# distribution.net
KiCad netlist of a schematic drawn in EAGLE
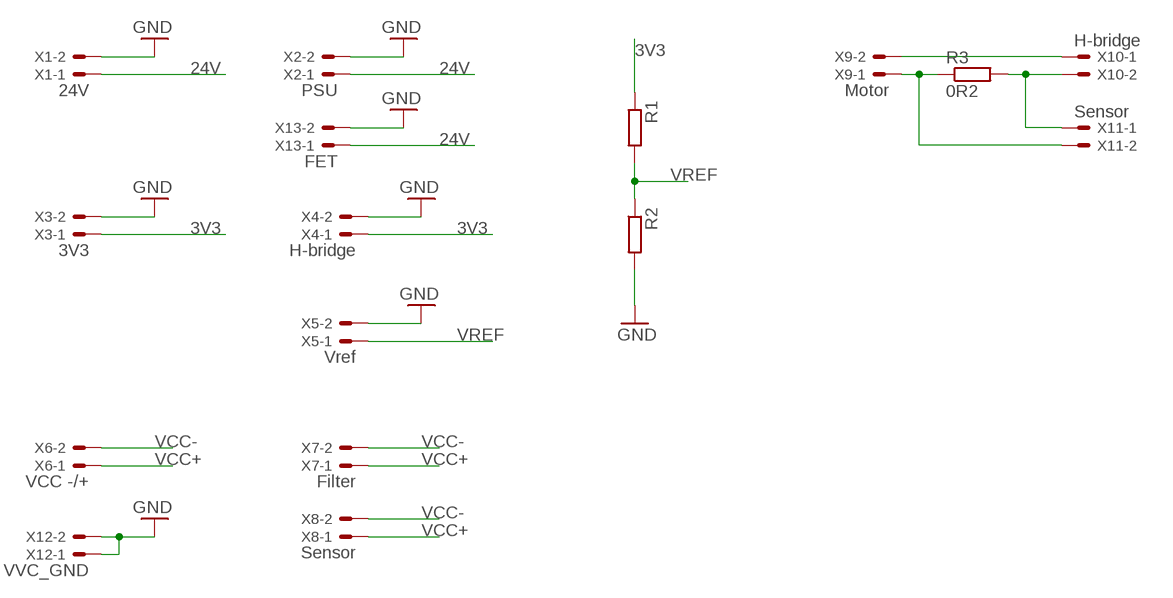
[diagram p0: schematic, sheet 1]

(export (version "E")
  (design (tool "Eeschema 10.0.6"))
  (components
    (comp (ref "R1")
      (value "R-EU_0207/10")
      (footprint "eagle-import:0207_10")
      (libsource (lib "eagle-import") (part "resistor_R-EU_0207/10"))
    )
    (comp (ref "R2")
      (value "R-EU_0207/10")
      (footprint "eagle-import:0207_10")
      (libsource (lib "eagle-import") (part "resistor_R-EU_0207/10"))
    )
    (comp (ref "R3")
      (value "0R2")
      (footprint "eagle-import:0414_15")
      (libsource (lib "eagle-import") (part "R-EU_0414/15"))
    )
    (comp (ref "X1")
      (value "24V")
      (footprint "eagle-import:22-23-2021")
      (fields (field (name "MF") "MOLEX") (field (name "MPN") "22-23-2021"))
      (libsource (lib "eagle-import") (part "22-23-2021"))
    )
    (comp (ref "X2")
      (value "PSU")
      (footprint "eagle-import:22-23-2021")
      (fields (field (name "MF") "MOLEX") (field (name "MPN") "22-23-2021"))
      (libsource (lib "eagle-import") (part "22-23-2021"))
    )
    (comp (ref "X3")
      (value "3V3")
      (footprint "eagle-import:22-23-2021")
      (fields (field (name "MF") "MOLEX") (field (name "MPN") "22-23-2021"))
      (libsource (lib "eagle-import") (part "22-23-2021"))
    )
    (comp (ref "X4")
      (value "H-bridge")
      (footprint "eagle-import:22-23-2021")
      (fields (field (name "MF") "MOLEX") (field (name "MPN") "22-23-2021"))
      (libsource (lib "eagle-import") (part "22-23-2021"))
    )
    (comp (ref "X5")
      (value "Vref")
      (footprint "eagle-import:22-23-2021")
      (fields (field (name "MF") "MOLEX") (field (name "MPN") "22-23-2021"))
      (libsource (lib "eagle-import") (part "22-23-2021"))
    )
    (comp (ref "X6")
      (value "VCC -/+")
      (footprint "eagle-import:22-23-2021")
      (fields (field (name "MF") "MOLEX") (field (name "MPN") "22-23-2021"))
      (libsource (lib "eagle-import") (part "22-23-2021"))
    )
    (comp (ref "X7")
      (value "Filter")
      (footprint "eagle-import:22-23-2021")
      (fields (field (name "MF") "MOLEX") (field (name "MPN") "22-23-2021"))
      (libsource (lib "eagle-import") (part "22-23-2021"))
    )
    (comp (ref "X8")
      (value "Sensor")
      (footprint "eagle-import:22-23-2021")
      (fields (field (name "MF") "MOLEX") (field (name "MPN") "22-23-2021"))
      (libsource (lib "eagle-import") (part "22-23-2021"))
    )
    (comp (ref "X9")
      (value "Motor")
      (footprint "eagle-import:22-23-2021")
      (fields (field (name "MF") "MOLEX") (field (name "MPN") "22-23-2021"))
      (libsource (lib "eagle-import") (part "22-23-2021"))
    )
    (comp (ref "X10")
      (value "H-bridge")
      (footprint "eagle-import:22-23-2021")
      (fields (field (name "MF") "MOLEX") (field (name "MPN") "22-23-2021"))
      (libsource (lib "eagle-import") (part "22-23-2021"))
    )
    (comp (ref "X11")
      (value "Sensor")
      (footprint "eagle-import:22-23-2021")
      (fields (field (name "MF") "MOLEX") (field (name "MPN") "22-23-2021"))
      (libsource (lib "eagle-import") (part "22-23-2021"))
    )
    (comp (ref "X12")
      (value "VVC_GND")
      (footprint "eagle-import:22-23-2021")
      (fields (field (name "MF") "MOLEX") (field (name "MPN") "22-23-2021"))
      (libsource (lib "eagle-import") (part "22-23-2021"))
    )
    (comp (ref "X13")
      (value "FET")
      (footprint "eagle-import:22-23-2021")
      (fields (field (name "MF") "MOLEX") (field (name "MPN") "22-23-2021"))
      (libsource (lib "eagle-import") (part "22-23-2021"))
    )
  )
  (nets
    (net (code "1") (name "/3V3") (class "Default")
      (node (ref "R1") (pin "1") (pinfunction "1_1") (pintype "passive"))
      (node (ref "X3") (pin "1") (pinfunction "S_1") (pintype "passive"))
      (node (ref "X4") (pin "1") (pinfunction "S_1") (pintype "passive"))
    )
    (net (code "2") (name "/24V") (class "Default")
      (node (ref "X1") (pin "1") (pinfunction "S_1") (pintype "passive"))
      (node (ref "X13") (pin "1") (pinfunction "S_1") (pintype "passive"))
      (node (ref "X2") (pin "1") (pinfunction "S_1") (pintype "passive"))
    )
    (net (code "3") (name "/VCC+") (class "Default")
      (node (ref "X6") (pin "1") (pinfunction "S_1") (pintype "passive"))
      (node (ref "X7") (pin "1") (pinfunction "S_1") (pintype "passive"))
      (node (ref "X8") (pin "1") (pinfunction "S_1") (pintype "passive"))
    )
    (net (code "4") (name "/VCC-") (class "Default")
      (node (ref "X6") (pin "2") (pinfunction "S_2") (pintype "passive"))
      (node (ref "X7") (pin "2") (pinfunction "S_2") (pintype "passive"))
      (node (ref "X8") (pin "2") (pinfunction "S_2") (pintype "passive"))
    )
    (net (code "5") (name "/VREF") (class "Default")
      (node (ref "R1") (pin "2") (pinfunction "2_2") (pintype "passive"))
      (node (ref "R2") (pin "1") (pinfunction "1_1") (pintype "passive"))
      (node (ref "X5") (pin "1") (pinfunction "S_1") (pintype "passive"))
    )
    (net (code "6") (name "GND") (class "Default")
      (node (ref "R2") (pin "2") (pinfunction "2_2") (pintype "passive"))
      (node (ref "X1") (pin "2") (pinfunction "S_2") (pintype "passive"))
      (node (ref "X12") (pin "1") (pinfunction "S_1") (pintype "passive"))
      (node (ref "X12") (pin "2") (pinfunction "S_2") (pintype "passive"))
      (node (ref "X13") (pin "2") (pinfunction "S_2") (pintype "passive"))
      (node (ref "X2") (pin "2") (pinfunction "S_2") (pintype "passive"))
      (node (ref "X3") (pin "2") (pinfunction "S_2") (pintype "passive"))
      (node (ref "X4") (pin "2") (pinfunction "S_2") (pintype "passive"))
      (node (ref "X5") (pin "2") (pinfunction "S_2") (pintype "passive"))
    )
    (net (code "7") (name "Net-(X10A-S)") (class "Default")
      (node (ref "X10") (pin "1") (pinfunction "S_1") (pintype "passive"))
      (node (ref "X9") (pin "2") (pinfunction "S_2") (pintype "passive"))
    )
    (net (code "8") (name "Net-(X10B-S)") (class "Default")
      (node (ref "R3") (pin "2") (pinfunction "2_2") (pintype "passive"))
      (node (ref "X10") (pin "2") (pinfunction "S_2") (pintype "passive"))
      (node (ref "X11") (pin "1") (pinfunction "S_1") (pintype "passive"))
    )
    (net (code "9") (name "Net-(X11B-S)") (class "Default")
      (node (ref "R3") (pin "1") (pinfunction "1_1") (pintype "passive"))
      (node (ref "X11") (pin "2") (pinfunction "S_2") (pintype "passive"))
      (node (ref "X9") (pin "1") (pinfunction "S_1") (pintype "passive"))
    )
  )
)
